# 06_LMS7002M_Power.net
KiCad netlist of a schematic drawn in Altium Designer
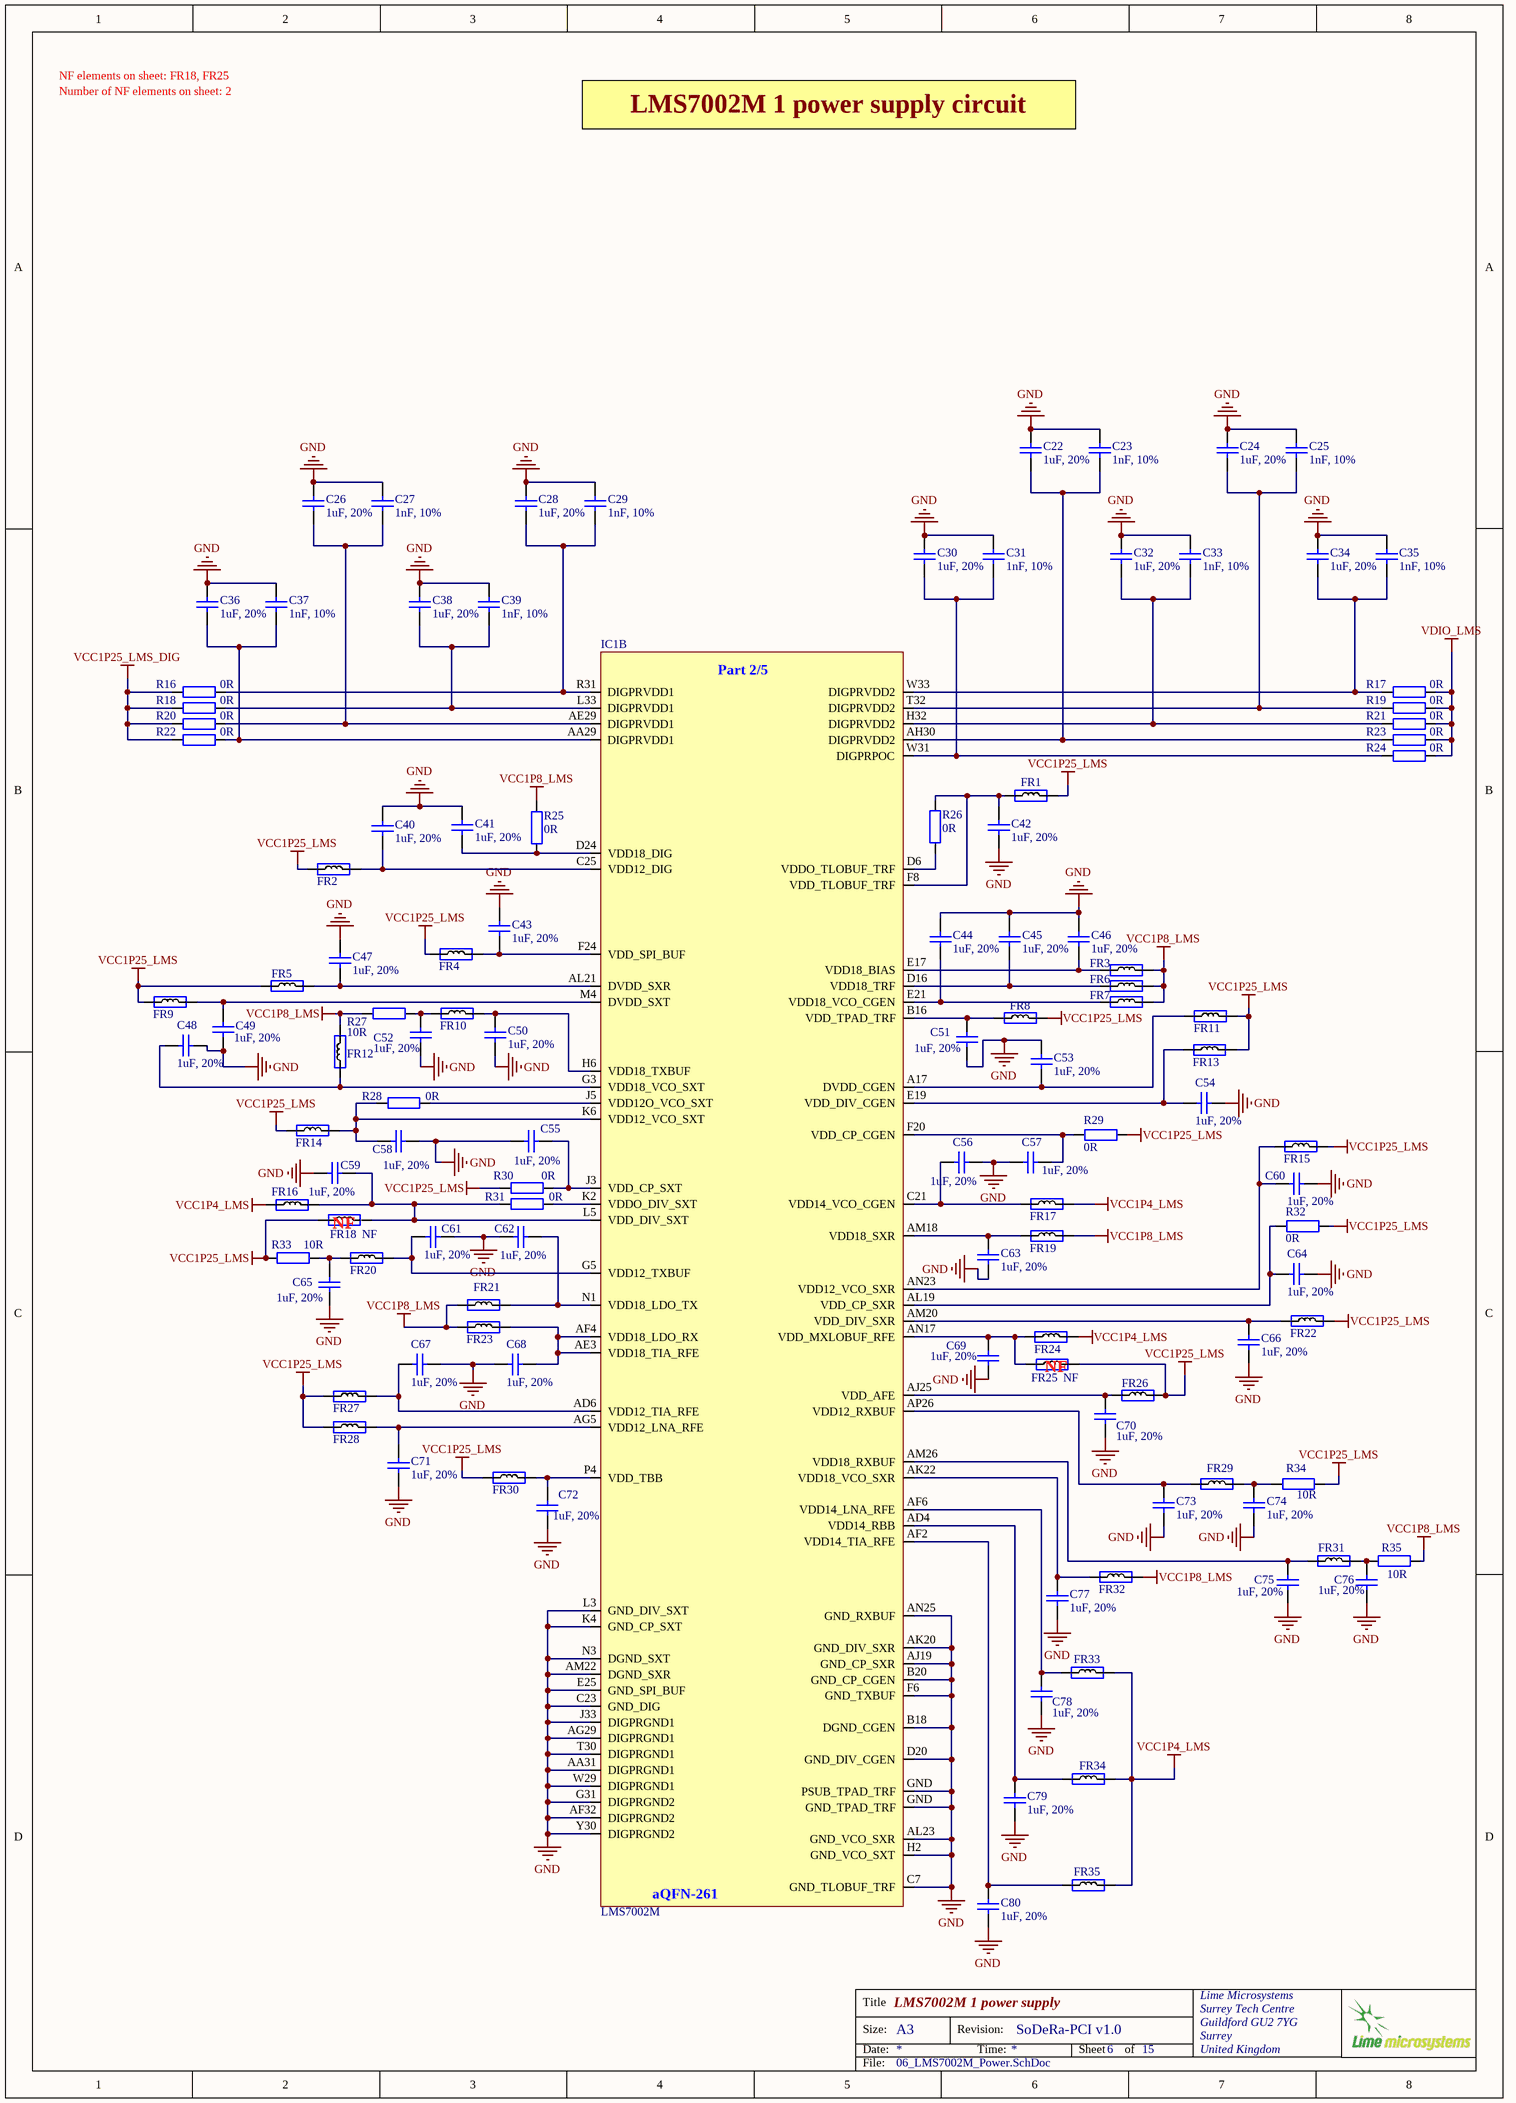
[diagram p0: 06_LMS7002M_Power.SchDoc]

(export (version "E")
  (design (tool "Eeschema 10.0.6"))
  (components
    (comp (ref "C22")
      (value "1uF, 20%")
      (footprint "LimeMicroAltiumLib_pcbLib:CAP0201")
      (fields (field (name "TOLERANCE") "±20%") (field (name "MANUFACTURER") "TDK Corporation"))
      (libsource (lib "LimeMicroAltiumLib_schLib") (part "Cap_0402"))
    )
    (comp (ref "C23")
      (value "1nF, 10%")
      (footprint "LimeMicroAltiumLib_pcbLib:CAP0201")
      (fields (field (name "TOLERANCE") "±10%") (field (name "MANUFACTURER") "TDK Corporation"))
      (libsource (lib "LimeMicroAltiumLib_schLib") (part "Cap_0402"))
    )
    (comp (ref "C24")
      (value "1uF, 20%")
      (footprint "LimeMicroAltiumLib_pcbLib:CAP0201")
      (fields (field (name "TOLERANCE") "±20%") (field (name "MANUFACTURER") "TDK Corporation"))
      (libsource (lib "LimeMicroAltiumLib_schLib") (part "Cap_0402"))
    )
    (comp (ref "C25")
      (value "1nF, 10%")
      (footprint "LimeMicroAltiumLib_pcbLib:CAP0201")
      (fields (field (name "TOLERANCE") "±10%") (field (name "MANUFACTURER") "TDK Corporation"))
      (libsource (lib "LimeMicroAltiumLib_schLib") (part "Cap_0402"))
    )
    (comp (ref "C26")
      (value "1uF, 20%")
      (footprint "LimeMicroAltiumLib_pcbLib:CAP0201")
      (fields (field (name "TOLERANCE") "±20%") (field (name "MANUFACTURER") "TDK Corporation"))
      (libsource (lib "LimeMicroAltiumLib_schLib") (part "Cap_0402"))
    )
    (comp (ref "C27")
      (value "1nF, 10%")
      (footprint "LimeMicroAltiumLib_pcbLib:CAP0201")
      (fields (field (name "TOLERANCE") "±10%") (field (name "MANUFACTURER") "TDK Corporation"))
      (libsource (lib "LimeMicroAltiumLib_schLib") (part "Cap_0402"))
    )
    (comp (ref "C28")
      (value "1uF, 20%")
      (footprint "LimeMicroAltiumLib_pcbLib:CAP0201")
      (fields (field (name "TOLERANCE") "±20%") (field (name "MANUFACTURER") "TDK Corporation"))
      (libsource (lib "LimeMicroAltiumLib_schLib") (part "Cap_0402"))
    )
    (comp (ref "C29")
      (value "1nF, 10%")
      (footprint "LimeMicroAltiumLib_pcbLib:CAP0201")
      (fields (field (name "TOLERANCE") "±10%") (field (name "MANUFACTURER") "TDK Corporation"))
      (libsource (lib "LimeMicroAltiumLib_schLib") (part "Cap_0402"))
    )
    (comp (ref "C30")
      (value "1uF, 20%")
      (footprint "LimeMicroAltiumLib_pcbLib:CAP0201")
      (fields (field (name "TOLERANCE") "±20%") (field (name "MANUFACTURER") "TDK Corporation"))
      (libsource (lib "LimeMicroAltiumLib_schLib") (part "Cap_0402"))
    )
    (comp (ref "C31")
      (value "1nF, 10%")
      (footprint "LimeMicroAltiumLib_pcbLib:CAP0201")
      (fields (field (name "TOLERANCE") "±10%") (field (name "MANUFACTURER") "TDK Corporation"))
      (libsource (lib "LimeMicroAltiumLib_schLib") (part "Cap_0402"))
    )
    (comp (ref "C32")
      (value "1uF, 20%")
      (footprint "LimeMicroAltiumLib_pcbLib:CAP0201")
      (fields (field (name "TOLERANCE") "±20%") (field (name "MANUFACTURER") "TDK Corporation"))
      (libsource (lib "LimeMicroAltiumLib_schLib") (part "Cap_0402"))
    )
    (comp (ref "C33")
      (value "1nF, 10%")
      (footprint "LimeMicroAltiumLib_pcbLib:CAP0201")
      (fields (field (name "TOLERANCE") "±10%") (field (name "MANUFACTURER") "TDK Corporation"))
      (libsource (lib "LimeMicroAltiumLib_schLib") (part "Cap_0402"))
    )
    (comp (ref "C34")
      (value "1uF, 20%")
      (footprint "LimeMicroAltiumLib_pcbLib:CAP0201")
      (fields (field (name "TOLERANCE") "±20%") (field (name "MANUFACTURER") "TDK Corporation"))
      (libsource (lib "LimeMicroAltiumLib_schLib") (part "Cap_0402"))
    )
    (comp (ref "C35")
      (value "1nF, 10%")
      (footprint "LimeMicroAltiumLib_pcbLib:CAP0201")
      (fields (field (name "TOLERANCE") "±10%") (field (name "MANUFACTURER") "TDK Corporation"))
      (libsource (lib "LimeMicroAltiumLib_schLib") (part "Cap_0402"))
    )
    (comp (ref "C36")
      (value "1uF, 20%")
      (footprint "LimeMicroAltiumLib_pcbLib:CAP0201")
      (fields (field (name "TOLERANCE") "±20%") (field (name "MANUFACTURER") "TDK Corporation"))
      (libsource (lib "LimeMicroAltiumLib_schLib") (part "Cap_0402"))
    )
    (comp (ref "C37")
      (value "1nF, 10%")
      (footprint "LimeMicroAltiumLib_pcbLib:CAP0201")
      (fields (field (name "TOLERANCE") "±10%") (field (name "MANUFACTURER") "TDK Corporation"))
      (libsource (lib "LimeMicroAltiumLib_schLib") (part "Cap_0402"))
    )
    (comp (ref "C38")
      (value "1uF, 20%")
      (footprint "LimeMicroAltiumLib_pcbLib:CAP0201")
      (fields (field (name "TOLERANCE") "±20%") (field (name "MANUFACTURER") "TDK Corporation"))
      (libsource (lib "LimeMicroAltiumLib_schLib") (part "Cap_0402"))
    )
    (comp (ref "C39")
      (value "1nF, 10%")
      (footprint "LimeMicroAltiumLib_pcbLib:CAP0201")
      (fields (field (name "TOLERANCE") "±10%") (field (name "MANUFACTURER") "TDK Corporation"))
      (libsource (lib "LimeMicroAltiumLib_schLib") (part "Cap_0402"))
    )
    (comp (ref "C40")
      (value "1uF, 20%")
      (footprint "LimeMicroAltiumLib_pcbLib:CAP0201")
      (fields (field (name "TOLERANCE") "±20%") (field (name "MANUFACTURER") "TDK Corporation"))
      (libsource (lib "LimeMicroAltiumLib_schLib") (part "Cap_0402"))
    )
    (comp (ref "C41")
      (value "1uF, 20%")
      (footprint "LimeMicroAltiumLib_pcbLib:CAP0201")
      (fields (field (name "TOLERANCE") "±20%") (field (name "MANUFACTURER") "TDK Corporation"))
      (libsource (lib "LimeMicroAltiumLib_schLib") (part "Cap_0402"))
    )
    (comp (ref "C42")
      (value "1uF, 20%")
      (footprint "LimeMicroAltiumLib_pcbLib:CAP0201")
      (fields (field (name "TOLERANCE") "±20%") (field (name "MANUFACTURER") "TDK Corporation"))
      (libsource (lib "LimeMicroAltiumLib_schLib") (part "Cap_0402"))
    )
    (comp (ref "C43")
      (value "1uF, 20%")
      (footprint "LimeMicroAltiumLib_pcbLib:CAP0201")
      (fields (field (name "TOLERANCE") "±20%") (field (name "MANUFACTURER") "TDK Corporation"))
      (libsource (lib "LimeMicroAltiumLib_schLib") (part "Cap_0402"))
    )
    (comp (ref "C44")
      (value "1uF, 20%")
      (footprint "LimeMicroAltiumLib_pcbLib:CAP0201")
      (fields (field (name "TOLERANCE") "±20%") (field (name "MANUFACTURER") "TDK Corporation"))
      (libsource (lib "LimeMicroAltiumLib_schLib") (part "Cap_0402"))
    )
    (comp (ref "C45")
      (value "1uF, 20%")
      (footprint "LimeMicroAltiumLib_pcbLib:CAP0201")
      (fields (field (name "TOLERANCE") "±20%") (field (name "MANUFACTURER") "TDK Corporation"))
      (libsource (lib "LimeMicroAltiumLib_schLib") (part "Cap_0402"))
    )
    (comp (ref "C46")
      (value "1uF, 20%")
      (footprint "LimeMicroAltiumLib_pcbLib:CAP0201")
      (fields (field (name "TOLERANCE") "±20%") (field (name "MANUFACTURER") "TDK Corporation"))
      (libsource (lib "LimeMicroAltiumLib_schLib") (part "Cap_0402"))
    )
    (comp (ref "C47")
      (value "1uF, 20%")
      (footprint "LimeMicroAltiumLib_pcbLib:CAP0201")
      (fields (field (name "TOLERANCE") "±20%") (field (name "MANUFACTURER") "TDK Corporation"))
      (libsource (lib "LimeMicroAltiumLib_schLib") (part "Cap_0402"))
    )
    (comp (ref "C48")
      (value "1uF, 20%")
      (footprint "LimeMicroAltiumLib_pcbLib:CAP0201")
      (fields (field (name "TOLERANCE") "±20%") (field (name "MANUFACTURER") "TDK Corporation"))
      (libsource (lib "LimeMicroAltiumLib_schLib") (part "Cap_0402"))
    )
    (comp (ref "C49")
      (value "1uF, 20%")
      (footprint "LimeMicroAltiumLib_pcbLib:CAP0201")
      (fields (field (name "TOLERANCE") "±20%") (field (name "MANUFACTURER") "TDK Corporation"))
      (libsource (lib "LimeMicroAltiumLib_schLib") (part "Cap_0402"))
    )
    (comp (ref "C50")
      (value "1uF, 20%")
      (footprint "LimeMicroAltiumLib_pcbLib:CAP0201")
      (fields (field (name "TOLERANCE") "±20%") (field (name "MANUFACTURER") "TDK Corporation"))
      (libsource (lib "LimeMicroAltiumLib_schLib") (part "Cap_0402"))
    )
    (comp (ref "C51")
      (value "1uF, 20%")
      (footprint "LimeMicroAltiumLib_pcbLib:CAP0201")
      (fields (field (name "TOLERANCE") "±20%") (field (name "MANUFACTURER") "TDK Corporation"))
      (libsource (lib "LimeMicroAltiumLib_schLib") (part "Cap_0402"))
    )
    (comp (ref "C52")
      (value "1uF, 20%")
      (footprint "LimeMicroAltiumLib_pcbLib:CAP0201")
      (fields (field (name "TOLERANCE") "±20%") (field (name "MANUFACTURER") "TDK Corporation"))
      (libsource (lib "LimeMicroAltiumLib_schLib") (part "Cap_0402"))
    )
    (comp (ref "C53")
      (value "1uF, 20%")
      (footprint "LimeMicroAltiumLib_pcbLib:CAP0201")
      (fields (field (name "TOLERANCE") "±20%") (field (name "MANUFACTURER") "TDK Corporation"))
      (libsource (lib "LimeMicroAltiumLib_schLib") (part "Cap_0402"))
    )
    (comp (ref "C54")
      (value "1uF, 20%")
      (footprint "LimeMicroAltiumLib_pcbLib:CAP0201")
      (fields (field (name "TOLERANCE") "±20%") (field (name "MANUFACTURER") "TDK Corporation"))
      (libsource (lib "LimeMicroAltiumLib_schLib") (part "Cap_0402"))
    )
    (comp (ref "C55")
      (value "1uF, 20%")
      (footprint "LimeMicroAltiumLib_pcbLib:CAP0201")
      (fields (field (name "TOLERANCE") "±20%") (field (name "MANUFACTURER") "TDK Corporation"))
      (libsource (lib "LimeMicroAltiumLib_schLib") (part "Cap_0402"))
    )
    (comp (ref "C56")
      (value "1uF, 20%")
      (footprint "LimeMicroAltiumLib_pcbLib:CAP0201")
      (fields (field (name "TOLERANCE") "±20%") (field (name "MANUFACTURER") "TDK Corporation"))
      (libsource (lib "LimeMicroAltiumLib_schLib") (part "Cap_0402"))
    )
    (comp (ref "C57")
      (value "1uF, 20%")
      (footprint "LimeMicroAltiumLib_pcbLib:CAP0201")
      (fields (field (name "TOLERANCE") "±20%") (field (name "MANUFACTURER") "TDK Corporation"))
      (libsource (lib "LimeMicroAltiumLib_schLib") (part "Cap_0402"))
    )
    (comp (ref "C58")
      (value "1uF, 20%")
      (footprint "LimeMicroAltiumLib_pcbLib:CAP0201")
      (fields (field (name "TOLERANCE") "±20%") (field (name "MANUFACTURER") "TDK Corporation"))
      (libsource (lib "LimeMicroAltiumLib_schLib") (part "Cap_0402"))
    )
    (comp (ref "C59")
      (value "1uF, 20%")
      (footprint "LimeMicroAltiumLib_pcbLib:CAP0201")
      (fields (field (name "TOLERANCE") "±20%") (field (name "MANUFACTURER") "TDK Corporation"))
      (libsource (lib "LimeMicroAltiumLib_schLib") (part "Cap_0402"))
    )
    (comp (ref "C60")
      (value "1uF, 20%")
      (footprint "LimeMicroAltiumLib_pcbLib:CAP0201")
      (fields (field (name "TOLERANCE") "±20%") (field (name "MANUFACTURER") "TDK Corporation"))
      (libsource (lib "LimeMicroAltiumLib_schLib") (part "Cap_0402"))
    )
    (comp (ref "C61")
      (value "1uF, 20%")
      (footprint "LimeMicroAltiumLib_pcbLib:CAP0201")
      (fields (field (name "TOLERANCE") "±20%") (field (name "MANUFACTURER") "TDK Corporation"))
      (libsource (lib "LimeMicroAltiumLib_schLib") (part "Cap_0402"))
    )
    (comp (ref "C62")
      (value "1uF, 20%")
      (footprint "LimeMicroAltiumLib_pcbLib:CAP0201")
      (fields (field (name "TOLERANCE") "±20%") (field (name "MANUFACTURER") "TDK Corporation"))
      (libsource (lib "LimeMicroAltiumLib_schLib") (part "Cap_0402"))
    )
    (comp (ref "C63")
      (value "1uF, 20%")
      (footprint "LimeMicroAltiumLib_pcbLib:CAP0201")
      (fields (field (name "TOLERANCE") "±20%") (field (name "MANUFACTURER") "TDK Corporation"))
      (libsource (lib "LimeMicroAltiumLib_schLib") (part "Cap_0402"))
    )
    (comp (ref "C64")
      (value "1uF, 20%")
      (footprint "LimeMicroAltiumLib_pcbLib:CAP0201")
      (fields (field (name "TOLERANCE") "±20%") (field (name "MANUFACTURER") "TDK Corporation"))
      (libsource (lib "LimeMicroAltiumLib_schLib") (part "Cap_0402"))
    )
    (comp (ref "C65")
      (value "1uF, 20%")
      (footprint "LimeMicroAltiumLib_pcbLib:CAP0201")
      (fields (field (name "TOLERANCE") "±20%") (field (name "MANUFACTURER") "TDK Corporation"))
      (libsource (lib "LimeMicroAltiumLib_schLib") (part "Cap_0402"))
    )
    (comp (ref "C66")
      (value "1uF, 20%")
      (footprint "LimeMicroAltiumLib_pcbLib:CAP0201")
      (fields (field (name "TOLERANCE") "±20%") (field (name "MANUFACTURER") "TDK Corporation"))
      (libsource (lib "LimeMicroAltiumLib_schLib") (part "Cap_0402"))
    )
    (comp (ref "C67")
      (value "1uF, 20%")
      (footprint "LimeMicroAltiumLib_pcbLib:CAP0201")
      (fields (field (name "TOLERANCE") "±20%") (field (name "MANUFACTURER") "TDK Corporation"))
      (libsource (lib "LimeMicroAltiumLib_schLib") (part "Cap_0402"))
    )
    (comp (ref "C68")
      (value "1uF, 20%")
      (footprint "LimeMicroAltiumLib_pcbLib:CAP0201")
      (fields (field (name "TOLERANCE") "±20%") (field (name "MANUFACTURER") "TDK Corporation"))
      (libsource (lib "LimeMicroAltiumLib_schLib") (part "Cap_0402"))
    )
    (comp (ref "C69")
      (value "1uF, 20%")
      (footprint "LimeMicroAltiumLib_pcbLib:CAP0201")
      (fields (field (name "TOLERANCE") "±20%") (field (name "MANUFACTURER") "TDK Corporation"))
      (libsource (lib "LimeMicroAltiumLib_schLib") (part "Cap_0402"))
    )
    (comp (ref "C70")
      (value "1uF, 20%")
      (footprint "LimeMicroAltiumLib_pcbLib:CAP0201")
      (fields (field (name "TOLERANCE") "±20%") (field (name "MANUFACTURER") "TDK Corporation"))
      (libsource (lib "LimeMicroAltiumLib_schLib") (part "Cap_0402"))
    )
    (comp (ref "C71")
      (value "1uF, 20%")
      (footprint "LimeMicroAltiumLib_pcbLib:CAP0201")
      (fields (field (name "TOLERANCE") "±20%") (field (name "MANUFACTURER") "TDK Corporation"))
      (libsource (lib "LimeMicroAltiumLib_schLib") (part "Cap_0402"))
    )
    (comp (ref "C72")
      (value "1uF, 20%")
      (footprint "LimeMicroAltiumLib_pcbLib:CAP0201")
      (fields (field (name "TOLERANCE") "±20%") (field (name "MANUFACTURER") "TDK Corporation"))
      (libsource (lib "LimeMicroAltiumLib_schLib") (part "Cap_0402"))
    )
    (comp (ref "C73")
      (value "1uF, 20%")
      (footprint "LimeMicroAltiumLib_pcbLib:CAP0201")
      (fields (field (name "TOLERANCE") "±20%") (field (name "MANUFACTURER") "TDK Corporation"))
      (libsource (lib "LimeMicroAltiumLib_schLib") (part "Cap_0402"))
    )
    (comp (ref "C74")
      (value "1uF, 20%")
      (footprint "LimeMicroAltiumLib_pcbLib:CAP0201")
      (fields (field (name "TOLERANCE") "±20%") (field (name "MANUFACTURER") "TDK Corporation"))
      (libsource (lib "LimeMicroAltiumLib_schLib") (part "Cap_0402"))
    )
    (comp (ref "C75")
      (value "1uF, 20%")
      (footprint "LimeMicroAltiumLib_pcbLib:CAP0201")
      (fields (field (name "TOLERANCE") "±20%") (field (name "MANUFACTURER") "TDK Corporation"))
      (libsource (lib "LimeMicroAltiumLib_schLib") (part "Cap_0402"))
    )
    (comp (ref "C76")
      (value "1uF, 20%")
      (footprint "LimeMicroAltiumLib_pcbLib:CAP0201")
      (fields (field (name "TOLERANCE") "±20%") (field (name "MANUFACTURER") "TDK Corporation"))
      (libsource (lib "LimeMicroAltiumLib_schLib") (part "Cap_0402"))
    )
    (comp (ref "C77")
      (value "1uF, 20%")
      (footprint "LimeMicroAltiumLib_pcbLib:CAP0201")
      (fields (field (name "TOLERANCE") "±20%") (field (name "MANUFACTURER") "TDK Corporation"))
      (libsource (lib "LimeMicroAltiumLib_schLib") (part "Cap_0402"))
    )
    (comp (ref "C78")
      (value "1uF, 20%")
      (footprint "LimeMicroAltiumLib_pcbLib:CAP0201")
      (fields (field (name "TOLERANCE") "±20%") (field (name "MANUFACTURER") "TDK Corporation"))
      (libsource (lib "LimeMicroAltiumLib_schLib") (part "Cap_0402"))
    )
    (comp (ref "C79")
      (value "1uF, 20%")
      (footprint "LimeMicroAltiumLib_pcbLib:CAP0201")
      (fields (field (name "TOLERANCE") "±20%") (field (name "MANUFACTURER") "TDK Corporation"))
      (libsource (lib "LimeMicroAltiumLib_schLib") (part "Cap_0402"))
    )
    (comp (ref "C80")
      (value "1uF, 20%")
      (footprint "LimeMicroAltiumLib_pcbLib:CAP0201")
      (fields (field (name "TOLERANCE") "±20%") (field (name "MANUFACTURER") "TDK Corporation"))
      (libsource (lib "LimeMicroAltiumLib_schLib") (part "Cap_0402"))
    )
    (comp (ref "FR1")
      (value "Ferrite")
      (footprint "LimeMicroAltiumLib_pcbLib:RES0201")
      (fields (field (name "MANUFACTURER") "Taiyo Yuden"))
      (libsource (lib "LimeMicroAltiumLib_schLib") (part "Ferrite"))
    )
    (comp (ref "FR2")
      (value "Ferrite")
      (footprint "LimeMicroAltiumLib_pcbLib:RES0201")
      (fields (field (name "MANUFACTURER") "Taiyo Yuden"))
      (libsource (lib "LimeMicroAltiumLib_schLib") (part "Ferrite"))
    )
    (comp (ref "FR3")
      (value "Ferrite")
      (footprint "LimeMicroAltiumLib_pcbLib:RES0201")
      (fields (field (name "MANUFACTURER") "Taiyo Yuden"))
      (libsource (lib "LimeMicroAltiumLib_schLib") (part "Ferrite"))
    )
    (comp (ref "FR4")
      (value "Ferrite")
      (footprint "LimeMicroAltiumLib_pcbLib:RES0201")
      (fields (field (name "MANUFACTURER") "Taiyo Yuden"))
      (libsource (lib "LimeMicroAltiumLib_schLib") (part "Ferrite"))
    )
    (comp (ref "FR5")
      (value "Ferrite")
      (footprint "LimeMicroAltiumLib_pcbLib:RES0201")
      (fields (field (name "MANUFACTURER") "Taiyo Yuden"))
      (libsource (lib "LimeMicroAltiumLib_schLib") (part "Ferrite"))
    )
    (comp (ref "FR6")
      (value "Ferrite")
      (footprint "LimeMicroAltiumLib_pcbLib:RES0201")
      (fields (field (name "MANUFACTURER") "Taiyo Yuden"))
      (libsource (lib "LimeMicroAltiumLib_schLib") (part "Ferrite"))
    )
    (comp (ref "FR7")
      (value "Ferrite")
      (footprint "LimeMicroAltiumLib_pcbLib:RES0201")
      (fields (field (name "MANUFACTURER") "Taiyo Yuden"))
      (libsource (lib "LimeMicroAltiumLib_schLib") (part "Ferrite"))
    )
    (comp (ref "FR8")
      (value "Ferrite")
      (footprint "LimeMicroAltiumLib_pcbLib:RES0201")
      (fields (field (name "MANUFACTURER") "Taiyo Yuden"))
      (libsource (lib "LimeMicroAltiumLib_schLib") (part "Ferrite"))
    )
    (comp (ref "FR9")
      (value "Ferrite")
      (footprint "LimeMicroAltiumLib_pcbLib:RES0201")
      (fields (field (name "MANUFACTURER") "Taiyo Yuden"))
      (libsource (lib "LimeMicroAltiumLib_schLib") (part "Ferrite"))
    )
    (comp (ref "FR10")
      (value "Ferrite")
      (footprint "LimeMicroAltiumLib_pcbLib:RES0201")
      (fields (field (name "MANUFACTURER") "Taiyo Yuden"))
      (libsource (lib "LimeMicroAltiumLib_schLib") (part "Ferrite"))
    )
    (comp (ref "FR11")
      (value "Ferrite")
      (footprint "LimeMicroAltiumLib_pcbLib:RES0201")
      (fields (field (name "MANUFACTURER") "Taiyo Yuden"))
      (libsource (lib "LimeMicroAltiumLib_schLib") (part "Ferrite"))
    )
    (comp (ref "FR12")
      (value "Ferrite")
      (footprint "LimeMicroAltiumLib_pcbLib:RES0201")
      (fields (field (name "MANUFACTURER") "Taiyo Yuden"))
      (libsource (lib "LimeMicroAltiumLib_schLib") (part "Ferrite"))
    )
    (comp (ref "FR13")
      (value "Ferrite")
      (footprint "LimeMicroAltiumLib_pcbLib:RES0201")
      (fields (field (name "MANUFACTURER") "Taiyo Yuden"))
      (libsource (lib "LimeMicroAltiumLib_schLib") (part "Ferrite"))
    )
    (comp (ref "FR14")
      (value "Ferrite")
      (footprint "LimeMicroAltiumLib_pcbLib:RES0201")
      (fields (field (name "MANUFACTURER") "Taiyo Yuden"))
      (libsource (lib "LimeMicroAltiumLib_schLib") (part "Ferrite"))
    )
    (comp (ref "FR15")
      (value "Ferrite")
      (footprint "LimeMicroAltiumLib_pcbLib:RES0201")
      (fields (field (name "MANUFACTURER") "Taiyo Yuden"))
      (libsource (lib "LimeMicroAltiumLib_schLib") (part "Ferrite"))
    )
    (comp (ref "FR16")
      (value "Ferrite")
      (footprint "LimeMicroAltiumLib_pcbLib:RES0201")
      (fields (field (name "MANUFACTURER") "Taiyo Yuden"))
      (libsource (lib "LimeMicroAltiumLib_schLib") (part "Ferrite"))
    )
    (comp (ref "FR17")
      (value "Ferrite")
      (footprint "LimeMicroAltiumLib_pcbLib:RES0201")
      (fields (field (name "MANUFACTURER") "Taiyo Yuden"))
      (libsource (lib "LimeMicroAltiumLib_schLib") (part "Ferrite"))
    )
    (comp (ref "FR18")
      (value "Ferrite")
      (footprint "LimeMicroAltiumLib_pcbLib:RES0201")
      (fields (field (name "MANUFACTURER") "Taiyo Yuden") (field (name "ASSEMBLY INFO") "NF"))
      (libsource (lib "LimeMicroAltiumLib_schLib") (part "Ferrite"))
    )
    (comp (ref "FR19")
      (value "Ferrite")
      (footprint "LimeMicroAltiumLib_pcbLib:RES0201")
      (fields (field (name "MANUFACTURER") "Taiyo Yuden"))
      (libsource (lib "LimeMicroAltiumLib_schLib") (part "Ferrite"))
    )
    (comp (ref "FR20")
      (value "Ferrite")
      (footprint "LimeMicroAltiumLib_pcbLib:RES0201")
      (fields (field (name "MANUFACTURER") "Taiyo Yuden"))
      (libsource (lib "LimeMicroAltiumLib_schLib") (part "Ferrite"))
    )
    (comp (ref "FR21")
      (value "Ferrite")
      (footprint "LimeMicroAltiumLib_pcbLib:RES0201")
      (fields (field (name "MANUFACTURER") "Taiyo Yuden"))
      (libsource (lib "LimeMicroAltiumLib_schLib") (part "Ferrite"))
    )
    (comp (ref "FR22")
      (value "Ferrite")
      (footprint "LimeMicroAltiumLib_pcbLib:RES0201")
      (fields (field (name "MANUFACTURER") "Taiyo Yuden"))
      (libsource (lib "LimeMicroAltiumLib_schLib") (part "Ferrite"))
    )
    (comp (ref "FR23")
      (value "Ferrite")
      (footprint "LimeMicroAltiumLib_pcbLib:RES0201")
      (fields (field (name "MANUFACTURER") "Taiyo Yuden"))
      (libsource (lib "LimeMicroAltiumLib_schLib") (part "Ferrite"))
    )
    (comp (ref "FR24")
      (value "Ferrite")
      (footprint "LimeMicroAltiumLib_pcbLib:RES0201")
      (fields (field (name "MANUFACTURER") "Taiyo Yuden"))
      (libsource (lib "LimeMicroAltiumLib_schLib") (part "Ferrite"))
    )
    (comp (ref "FR25")
      (value "Ferrite")
      (footprint "LimeMicroAltiumLib_pcbLib:RES0201")
      (fields (field (name "MANUFACTURER") "Taiyo Yuden") (field (name "ASSEMBLY INFO") "NF"))
      (libsource (lib "LimeMicroAltiumLib_schLib") (part "Ferrite"))
    )
    (comp (ref "FR26")
      (value "Ferrite")
      (footprint "LimeMicroAltiumLib_pcbLib:RES0201")
      (fields (field (name "MANUFACTURER") "Taiyo Yuden"))
      (libsource (lib "LimeMicroAltiumLib_schLib") (part "Ferrite"))
    )
    (comp (ref "FR27")
      (value "Ferrite")
      (footprint "LimeMicroAltiumLib_pcbLib:RES0201")
      (fields (field (name "MANUFACTURER") "Taiyo Yuden"))
      (libsource (lib "LimeMicroAltiumLib_schLib") (part "Ferrite"))
    )
    (comp (ref "FR28")
      (value "Ferrite")
      (footprint "LimeMicroAltiumLib_pcbLib:RES0201")
      (fields (field (name "MANUFACTURER") "Taiyo Yuden"))
      (libsource (lib "LimeMicroAltiumLib_schLib") (part "Ferrite"))
    )
    (comp (ref "FR29")
      (value "Ferrite")
      (footprint "LimeMicroAltiumLib_pcbLib:RES0201")
      (fields (field (name "MANUFACTURER") "Taiyo Yuden"))
      (libsource (lib "LimeMicroAltiumLib_schLib") (part "Ferrite"))
    )
    (comp (ref "FR30")
      (value "Ferrite")
      (footprint "LimeMicroAltiumLib_pcbLib:RES0201")
      (fields (field (name "MANUFACTURER") "Taiyo Yuden"))
      (libsource (lib "LimeMicroAltiumLib_schLib") (part "Ferrite"))
    )
    (comp (ref "FR31")
      (value "Ferrite")
      (footprint "LimeMicroAltiumLib_pcbLib:RES0201")
      (fields (field (name "MANUFACTURER") "Taiyo Yuden"))
      (libsource (lib "LimeMicroAltiumLib_schLib") (part "Ferrite"))
    )
    (comp (ref "FR32")
      (value "Ferrite")
      (footprint "LimeMicroAltiumLib_pcbLib:RES0201")
      (fields (field (name "MANUFACTURER") "Taiyo Yuden"))
      (libsource (lib "LimeMicroAltiumLib_schLib") (part "Ferrite"))
    )
    (comp (ref "FR33")
      (value "Ferrite")
      (footprint "LimeMicroAltiumLib_pcbLib:RES0201")
      (fields (field (name "MANUFACTURER") "Taiyo Yuden"))
      (libsource (lib "LimeMicroAltiumLib_schLib") (part "Ferrite"))
    )
    (comp (ref "FR34")
      (value "Ferrite")
      (footprint "LimeMicroAltiumLib_pcbLib:RES0201")
      (fields (field (name "MANUFACTURER") "Taiyo Yuden"))
      (libsource (lib "LimeMicroAltiumLib_schLib") (part "Ferrite"))
    )
    (comp (ref "FR35")
      (value "Ferrite")
      (footprint "LimeMicroAltiumLib_pcbLib:RES0201")
      (fields (field (name "MANUFACTURER") "Taiyo Yuden"))
      (libsource (lib "LimeMicroAltiumLib_schLib") (part "Ferrite"))
    )
    (comp (ref "IC1")
      (value "LMS7002M")
      (footprint "LimeMicroAltiumLib_pcbLib:LMS7002M")
      (libsource (lib "LimeMicroAltiumLib_schLib") (part "LMS7002M"))
    )
    (comp (ref "R16")
      (value "0R")
      (footprint "LimeMicroAltiumLib_pcbLib:RES0402")
      (fields (field (name "MANUFACTURER") "Yageo") (field (name "TOLERANCE") "Jumper"))
      (libsource (lib "LimeMicroAltiumLib_schLib") (part "Res_0402"))
    )
    (comp (ref "R17")
      (value "0R")
      (footprint "LimeMicroAltiumLib_pcbLib:RES0402")
      (fields (field (name "MANUFACTURER") "Yageo") (field (name "TOLERANCE") "Jumper"))
      (libsource (lib "LimeMicroAltiumLib_schLib") (part "Res_0402"))
    )
    (comp (ref "R18")
      (value "0R")
      (footprint "LimeMicroAltiumLib_pcbLib:RES0402")
      (fields (field (name "MANUFACTURER") "Yageo") (field (name "TOLERANCE") "Jumper"))
      (libsource (lib "LimeMicroAltiumLib_schLib") (part "Res_0402"))
    )
    (comp (ref "R19")
      (value "0R")
      (footprint "LimeMicroAltiumLib_pcbLib:RES0402")
      (fields (field (name "MANUFACTURER") "Yageo") (field (name "TOLERANCE") "Jumper"))
      (libsource (lib "LimeMicroAltiumLib_schLib") (part "Res_0402"))
    )
    (comp (ref "R20")
      (value "0R")
      (footprint "LimeMicroAltiumLib_pcbLib:RES0402")
      (fields (field (name "MANUFACTURER") "Yageo") (field (name "TOLERANCE") "Jumper"))
      (libsource (lib "LimeMicroAltiumLib_schLib") (part "Res_0402"))
    )
    (comp (ref "R21")
      (value "0R")
      (footprint "LimeMicroAltiumLib_pcbLib:RES0402")
      (fields (field (name "MANUFACTURER") "Yageo") (field (name "TOLERANCE") "Jumper"))
      (libsource (lib "LimeMicroAltiumLib_schLib") (part "Res_0402"))
    )
    (comp (ref "R22")
      (value "0R")
      (footprint "LimeMicroAltiumLib_pcbLib:RES0402")
      (fields (field (name "MANUFACTURER") "Yageo") (field (name "TOLERANCE") "Jumper"))
      (libsource (lib "LimeMicroAltiumLib_schLib") (part "Res_0402"))
    )
    (comp (ref "R23")
      (value "0R")
      (footprint "LimeMicroAltiumLib_pcbLib:RES0402")
      (fields (field (name "MANUFACTURER") "Yageo") (field (name "TOLERANCE") "Jumper"))
      (libsource (lib "LimeMicroAltiumLib_schLib") (part "Res_0402"))
    )
    (comp (ref "R24")
      (value "0R")
      (footprint "LimeMicroAltiumLib_pcbLib:RES0402")
      (fields (field (name "MANUFACTURER") "Yageo") (field (name "TOLERANCE") "Jumper"))
      (libsource (lib "LimeMicroAltiumLib_schLib") (part "Res_0402"))
    )
    (comp (ref "R25")
      (value "0R")
      (footprint "LimeMicroAltiumLib_pcbLib:RES0201")
      (fields (field (name "MANUFACTURER") "Rohm Semiconductor") (field (name "TOLERANCE") "Jumper"))
      (libsource (lib "LimeMicroAltiumLib_schLib") (part "Res_0402"))
    )
    (comp (ref "R26")
      (value "0R")
      (footprint "LimeMicroAltiumLib_pcbLib:RES0201")
      (fields (field (name "MANUFACTURER") "Rohm Semiconductor") (field (name "TOLERANCE") "Jumper"))
      (libsource (lib "LimeMicroAltiumLib_schLib") (part "Res_0402"))
    )
    (comp (ref "R27")
      (value "10R")
      (footprint "LimeMicroAltiumLib_pcbLib:RES0201")
      (fields
        (field (name "MANUFACTURER") "Panasonic Electronic Components")
        (field (name "TOLERANCE") "±1%")
        (field (name "MANUFACTURER PART NUMBER") "ERJ-1GEF10R0C")
      )
      (libsource (lib "LimeMicroAltiumLib_schLib") (part "Res_0402"))
    )
    (comp (ref "R28")
      (value "0R")
      (footprint "LimeMicroAltiumLib_pcbLib:RES0201")
      (fields (field (name "MANUFACTURER") "Rohm Semiconductor") (field (name "TOLERANCE") "Jumper"))
      (libsource (lib "LimeMicroAltiumLib_schLib") (part "Res_0402"))
    )
    (comp (ref "R29")
      (value "0R")
      (footprint "LimeMicroAltiumLib_pcbLib:RES0201")
      (fields (field (name "MANUFACTURER") "Rohm Semiconductor") (field (name "TOLERANCE") "Jumper"))
      (libsource (lib "LimeMicroAltiumLib_schLib") (part "Res_0402"))
    )
    (comp (ref "R30")
      (value "0R")
      (footprint "LimeMicroAltiumLib_pcbLib:RES0201")
      (fields (field (name "MANUFACTURER") "Rohm Semiconductor") (field (name "TOLERANCE") "Jumper"))
      (libsource (lib "LimeMicroAltiumLib_schLib") (part "Res_0402"))
    )
    (comp (ref "R31")
      (value "0R")
      (footprint "LimeMicroAltiumLib_pcbLib:RES0201")
      (fields (field (name "MANUFACTURER") "Rohm Semiconductor") (field (name "TOLERANCE") "Jumper"))
      (libsource (lib "LimeMicroAltiumLib_schLib") (part "Res_0402"))
    )
    (comp (ref "R32")
      (value "0R")
      (footprint "LimeMicroAltiumLib_pcbLib:RES0201")
      (fields (field (name "MANUFACTURER") "Rohm Semiconductor") (field (name "TOLERANCE") "Jumper"))
      (libsource (lib "LimeMicroAltiumLib_schLib") (part "Res_0402"))
    )
    (comp (ref "R33")
      (value "10R")
      (footprint "LimeMicroAltiumLib_pcbLib:RES0201")
      (fields
        (field (name "MANUFACTURER") "Panasonic Electronic Components")
        (field (name "TOLERANCE") "±1%")
        (field (name "MANUFACTURER PART NUMBER") "ERJ-1GEF10R0C")
      )
      (libsource (lib "LimeMicroAltiumLib_schLib") (part "Res_0402"))
    )
    (comp (ref "R34")
      (value "10R")
      (footprint "LimeMicroAltiumLib_pcbLib:RES0201")
      (fields
        (field (name "MANUFACTURER") "Panasonic Electronic Components")
        (field (name "TOLERANCE") "±1%")
        (field (name "MANUFACTURER PART NUMBER") "ERJ-1GEF10R0C")
      )
      (libsource (lib "LimeMicroAltiumLib_schLib") (part "Res_0402"))
    )
    (comp (ref "R35")
      (value "10R")
      (footprint "LimeMicroAltiumLib_pcbLib:RES0201")
      (fields
        (field (name "MANUFACTURER") "Panasonic Electronic Components")
        (field (name "TOLERANCE") "±1%")
        (field (name "MANUFACTURER PART NUMBER") "ERJ-1GEF10R0C")
      )
      (libsource (lib "LimeMicroAltiumLib_schLib") (part "Res_0402"))
    )
  )
  (nets
    (net (code "1") (name "GND") (class "Default")
      (node (ref "C22") (pin "2") (pinfunction "2_2") (pintype "passive"))
      (node (ref "C23") (pin "2") (pinfunction "2_2") (pintype "passive"))
      (node (ref "C24") (pin "2") (pinfunction "2_2") (pintype "passive"))
      (node (ref "C25") (pin "2") (pinfunction "2_2") (pintype "passive"))
      (node (ref "C26") (pin "2") (pinfunction "2_2") (pintype "passive"))
      (node (ref "C27") (pin "2") (pinfunction "2_2") (pintype "passive"))
      (node (ref "C28") (pin "2") (pinfunction "2_2") (pintype "passive"))
      (node (ref "C29") (pin "2") (pinfunction "2_2") (pintype "passive"))
      (node (ref "C30") (pin "2") (pinfunction "2_2") (pintype "passive"))
      (node (ref "C31") (pin "2") (pinfunction "2_2") (pintype "passive"))
      (node (ref "C32") (pin "2") (pinfunction "2_2") (pintype "passive"))
      (node (ref "C33") (pin "2") (pinfunction "2_2") (pintype "passive"))
      (node (ref "C34") (pin "2") (pinfunction "2_2") (pintype "passive"))
      (node (ref "C35") (pin "2") (pinfunction "2_2") (pintype "passive"))
      (node (ref "C36") (pin "2") (pinfunction "2_2") (pintype "passive"))
      (node (ref "C37") (pin "2") (pinfunction "2_2") (pintype "passive"))
      (node (ref "C38") (pin "2") (pinfunction "2_2") (pintype "passive"))
      (node (ref "C39") (pin "2") (pinfunction "2_2") (pintype "passive"))
      (node (ref "C40") (pin "2") (pinfunction "2_2") (pintype "passive"))
      (node (ref "C41") (pin "2") (pinfunction "2_2") (pintype "passive"))
      (node (ref "C42") (pin "2") (pinfunction "2_2") (pintype "passive"))
      (node (ref "C43") (pin "2") (pinfunction "2_2") (pintype "passive"))
      (node (ref "C44") (pin "2") (pinfunction "2_2") (pintype "passive"))
      (node (ref "C45") (pin "2") (pinfunction "2_2") (pintype "passive"))
      (node (ref "C46") (pin "2") (pinfunction "2_2") (pintype "passive"))
      (node (ref "C47") (pin "2") (pinfunction "2_2") (pintype "passive"))
      (node (ref "C48") (pin "2") (pinfunction "2_2") (pintype "passive"))
      (node (ref "C49") (pin "2") (pinfunction "2_2") (pintype "passive"))
      (node (ref "C50") (pin "2") (pinfunction "2_2") (pintype "passive"))
      (node (ref "C51") (pin "2") (pinfunction "2_2") (pintype "passive"))
      (node (ref "C52") (pin "2") (pinfunction "2_2") (pintype "passive"))
      (node (ref "C53") (pin "2") (pinfunction "2_2") (pintype "passive"))
      (node (ref "C54") (pin "2") (pinfunction "2_2") (pintype "passive"))
      (node (ref "C55") (pin "2") (pinfunction "2_2") (pintype "passive"))
      (node (ref "C56") (pin "2") (pinfunction "2_2") (pintype "passive"))
      (node (ref "C57") (pin "2") (pinfunction "2_2") (pintype "passive"))
      (node (ref "C58") (pin "1") (pinfunction "1_1") (pintype "passive"))
      (node (ref "C59") (pin "2") (pinfunction "2_2") (pintype "passive"))
      (node (ref "C60") (pin "2") (pinfunction "2_2") (pintype "passive"))
      (node (ref "C61") (pin "2") (pinfunction "2_2") (pintype "passive"))
      (node (ref "C62") (pin "2") (pinfunction "2_2") (pintype "passive"))
      (node (ref "C63") (pin "2") (pinfunction "2_2") (pintype "passive"))
      (node (ref "C64") (pin "2") (pinfunction "2_2") (pintype "passive"))
      (node (ref "C65") (pin "2") (pinfunction "2_2") (pintype "passive"))
      (node (ref "C66") (pin "2") (pinfunction "2_2") (pintype "passive"))
      (node (ref "C67") (pin "2") (pinfunction "2_2") (pintype "passive"))
      (node (ref "C68") (pin "2") (pinfunction "2_2") (pintype "passive"))
      (node (ref "C69") (pin "2") (pinfunction "2_2") (pintype "passive"))
      (node (ref "C70") (pin "2") (pinfunction "2_2") (pintype "passive"))
      (node (ref "C71") (pin "2") (pinfunction "2_2") (pintype "passive"))
      (node (ref "C72") (pin "2") (pinfunction "2_2") (pintype "passive"))
      (node (ref "C73") (pin "2") (pinfunction "2_2") (pintype "passive"))
      (node (ref "C74") (pin "2") (pinfunction "2_2") (pintype "passive"))
      (node (ref "C75") (pin "2") (pinfunction "2_2") (pintype "passive"))
      (node (ref "C76") (pin "2") (pinfunction "2_2") (pintype "passive"))
      (node (ref "C77") (pin "2") (pinfunction "2_2") (pintype "passive"))
      (node (ref "C78") (pin "2") (pinfunction "2_2") (pintype "passive"))
      (node (ref "C79") (pin "2") (pinfunction "2_2") (pintype "passive"))
      (node (ref "C80") (pin "2") (pinfunction "2_2") (pintype "passive"))
      (node (ref "IC1") (pin "AA31") (pinfunction "DIGPRGND1_AA31") (pintype "passive"))
      (node (ref "IC1") (pin "AF32") (pinfunction "DIGPRGND2_AF32") (pintype "passive"))
      (node (ref "IC1") (pin "AG29") (pinfunction "DIGPRGND1_AG29") (pintype "passive"))
      (node (ref "IC1") (pin "AJ19") (pinfunction "GND_CP_SXR_AJ19") (pintype "passive"))
      (node (ref "IC1") (pin "AK20") (pinfunction "GND_DIV_SXR_AK20") (pintype "passive"))
      (node (ref "IC1") (pin "AL23") (pinfunction "GND_VCO_SXR_AL23") (pintype "passive"))
      (node (ref "IC1") (pin "AM22") (pinfunction "DGND_SXR_AM22") (pintype "passive"))
      (node (ref "IC1") (pin "AN25") (pinfunction "GND_RXBUF_AN25") (pintype "passive"))
      (node (ref "IC1") (pin "B18") (pinfunction "DGND_CGEN_B18") (pintype "passive"))
      (node (ref "IC1") (pin "B20") (pinfunction "GND_CP_CGEN_B20") (pintype "passive"))
      (node (ref "IC1") (pin "C23") (pinfunction "GND_DIG_C23") (pintype "passive"))
      (node (ref "IC1") (pin "C7") (pinfunction "GND_TLOBUF_TRF_C7") (pintype "passive"))
      (node (ref "IC1") (pin "D20") (pinfunction "GND_DIV_CGEN_D20") (pintype "passive"))
      (node (ref "IC1") (pin "E25") (pinfunction "GND_SPI_BUF_E25") (pintype "passive"))
      (node (ref "IC1") (pin "F6") (pinfunction "GND_TXBUF_F6") (pintype "passive"))
      (node (ref "IC1") (pin "G31") (pinfunction "DIGPRGND2_G31") (pintype "passive"))
      (node (ref "IC1") (pin "GND") (pinfunction "PSUB_TPAD_TRF_GND") (pintype "passive"))
      (node (ref "IC1") (pin "H2") (pinfunction "GND_VCO_SXT_H2") (pintype "passive"))
      (node (ref "IC1") (pin "J33") (pinfunction "DIGPRGND1_J33") (pintype "passive"))
      (node (ref "IC1") (pin "K4") (pinfunction "GND_CP_SXT_K4") (pintype "passive"))
      (node (ref "IC1") (pin "L3") (pinfunction "GND_DIV_SXT_L3") (pintype "passive"))
      (node (ref "IC1") (pin "N3") (pinfunction "DGND_SXT_N3") (pintype "passive"))
      (node (ref "IC1") (pin "T30") (pinfunction "DIGPRGND1_T30") (pintype "passive"))
      (node (ref "IC1") (pin "W29") (pinfunction "DIGPRGND1_W29") (pintype "passive"))
      (node (ref "IC1") (pin "Y30") (pinfunction "DIGPRGND2_Y30") (pintype "passive"))
    )
    (net (code "2") (name "Net-(C22-Pad1)") (class "Default")
      (node (ref "C22") (pin "1") (pinfunction "1_1") (pintype "passive"))
      (node (ref "C23") (pin "1") (pinfunction "1_1") (pintype "passive"))
      (node (ref "IC1") (pin "AH30") (pinfunction "DIGPRVDD2_AH30") (pintype "passive"))
      (node (ref "R23") (pin "2") (pinfunction "2_2") (pintype "passive"))
    )
    (net (code "3") (name "Net-(C24-Pad1)") (class "Default")
      (node (ref "C24") (pin "1") (pinfunction "1_1") (pintype "passive"))
      (node (ref "C25") (pin "1") (pinfunction "1_1") (pintype "passive"))
      (node (ref "IC1") (pin "T32") (pinfunction "DIGPRVDD2_T32") (pintype "passive"))
      (node (ref "R19") (pin "2") (pinfunction "2_2") (pintype "passive"))
    )
    (net (code "4") (name "Net-(C26-Pad1)") (class "Default")
      (node (ref "C26") (pin "1") (pinfunction "1_1") (pintype "passive"))
      (node (ref "C27") (pin "1") (pinfunction "1_1") (pintype "passive"))
      (node (ref "IC1") (pin "AE29") (pinfunction "DIGPRVDD1_AE29") (pintype "passive"))
      (node (ref "R20") (pin "1") (pinfunction "1_1") (pintype "passive"))
    )
    (net (code "5") (name "Net-(C28-Pad1)") (class "Default")
      (node (ref "C28") (pin "1") (pinfunction "1_1") (pintype "passive"))
      (node (ref "C29") (pin "1") (pinfunction "1_1") (pintype "passive"))
      (node (ref "IC1") (pin "R31") (pinfunction "DIGPRVDD1_R31") (pintype "passive"))
      (node (ref "R16") (pin "1") (pinfunction "1_1") (pintype "passive"))
    )
    (net (code "6") (name "Net-(C32-Pad1)") (class "Default")
      (node (ref "C32") (pin "1") (pinfunction "1_1") (pintype "passive"))
      (node (ref "C33") (pin "1") (pinfunction "1_1") (pintype "passive"))
      (node (ref "IC1") (pin "H32") (pinfunction "DIGPRVDD2_H32") (pintype "passive"))
      (node (ref "R21") (pin "2") (pinfunction "2_2") (pintype "passive"))
    )
    (net (code "7") (name "Net-(C34-Pad1)") (class "Default")
      (node (ref "C34") (pin "1") (pinfunction "1_1") (pintype "passive"))
      (node (ref "C35") (pin "1") (pinfunction "1_1") (pintype "passive"))
      (node (ref "IC1") (pin "W33") (pinfunction "DIGPRVDD2_W33") (pintype "passive"))
      (node (ref "R17") (pin "2") (pinfunction "2_2") (pintype "passive"))
    )
    (net (code "8") (name "Net-(C36-Pad1)") (class "Default")
      (node (ref "C36") (pin "1") (pinfunction "1_1") (pintype "passive"))
      (node (ref "C37") (pin "1") (pinfunction "1_1") (pintype "passive"))
      (node (ref "IC1") (pin "AA29") (pinfunction "DIGPRVDD1_AA29") (pintype "passive"))
      (node (ref "R22") (pin "1") (pinfunction "1_1") (pintype "passive"))
    )
    (net (code "9") (name "Net-(C38-Pad1)") (class "Default")
      (node (ref "C38") (pin "1") (pinfunction "1_1") (pintype "passive"))
      (node (ref "C39") (pin "1") (pinfunction "1_1") (pintype "passive"))
      (node (ref "IC1") (pin "L33") (pinfunction "DIGPRVDD1_L33") (pintype "passive"))
      (node (ref "R18") (pin "1") (pinfunction "1_1") (pintype "passive"))
    )
    (net (code "10") (name "Net-(C52-Pad1)") (class "Default")
      (node (ref "C52") (pin "1") (pinfunction "1_1") (pintype "passive"))
      (node (ref "FR10") (pin "1") (pinfunction "1_1") (pintype "passive"))
      (node (ref "R27") (pin "1") (pinfunction "1_1") (pintype "passive"))
    )
    (net (code "11") (name "Net-(C65-Pad1)") (class "Default")
      (node (ref "C65") (pin "1") (pinfunction "1_1") (pintype "passive"))
      (node (ref "FR20") (pin "1") (pinfunction "1_1") (pintype "passive"))
      (node (ref "R33") (pin "1") (pinfunction "1_1") (pintype "passive"))
    )
    (net (code "12") (name "Net-(C74-Pad1)") (class "Default")
      (node (ref "C74") (pin "1") (pinfunction "1_1") (pintype "passive"))
      (node (ref "FR29") (pin "2") (pinfunction "2_2") (pintype "passive"))
      (node (ref "R34") (pin "2") (pinfunction "2_2") (pintype "passive"))
    )
    (net (code "13") (name "Net-(C76-Pad1)") (class "Default")
      (node (ref "C76") (pin "1") (pinfunction "1_1") (pintype "passive"))
      (node (ref "FR31") (pin "2") (pinfunction "2_2") (pintype "passive"))
      (node (ref "R35") (pin "2") (pinfunction "2_2") (pintype "passive"))
    )
    (net (code "14") (name "Net-(IC1B-DIGPRPOC)") (class "Default")
      (node (ref "C30") (pin "1") (pinfunction "1_1") (pintype "passive"))
      (node (ref "C31") (pin "1") (pinfunction "1_1") (pintype "passive"))
      (node (ref "IC1") (pin "W31") (pinfunction "DIGPRPOC_W31") (pintype "passive"))
      (node (ref "R24") (pin "2") (pinfunction "2_2") (pintype "passive"))
    )
    (net (code "15") (name "Net-(IC1B-DVDD_CGEN)") (class "Default")
      (node (ref "C53") (pin "1") (pinfunction "1_1") (pintype "passive"))
      (node (ref "FR11") (pin "1") (pinfunction "1_1") (pintype "passive"))
      (node (ref "IC1") (pin "A17") (pinfunction "DVDD_CGEN_A17") (pintype "passive"))
    )
    (net (code "16") (name "Net-(IC1B-DVDD_SXR)") (class "Default")
      (node (ref "C47") (pin "1") (pinfunction "1_1") (pintype "passive"))
      (node (ref "FR5") (pin "2") (pinfunction "2_2") (pintype "passive"))
      (node (ref "IC1") (pin "AL21") (pinfunction "DVDD_SXR_AL21") (pintype "passive"))
    )
    (net (code "17") (name "Net-(IC1B-DVDD_SXT)") (class "Default")
      (node (ref "C49") (pin "1") (pinfunction "1_1") (pintype "passive"))
      (node (ref "FR9") (pin "2") (pinfunction "2_2") (pintype "passive"))
      (node (ref "IC1") (pin "M4") (pinfunction "DVDD_SXT_M4") (pintype "passive"))
    )
    (net (code "18") (name "Net-(IC1B-VDD12O_VCO_SXT)") (class "Default")
      (node (ref "IC1") (pin "J5") (pinfunction "VDD12O_VCO_SXT_J5") (pintype "passive"))
      (node (ref "R28") (pin "1") (pinfunction "1_1") (pintype "passive"))
    )
    (net (code "19") (name "Net-(IC1B-VDD12_DIG)") (class "Default")
      (node (ref "C40") (pin "1") (pinfunction "1_1") (pintype "passive"))
      (node (ref "FR2") (pin "2") (pinfunction "2_2") (pintype "passive"))
      (node (ref "IC1") (pin "C25") (pinfunction "VDD12_DIG_C25") (pintype "passive"))
    )
    (net (code "20") (name "Net-(IC1B-VDD12_LNA_RFE)") (class "Default")
      (node (ref "C71") (pin "1") (pinfunction "1_1") (pintype "passive"))
      (node (ref "FR28") (pin "2") (pinfunction "2_2") (pintype "passive"))
      (node (ref "IC1") (pin "AG5") (pinfunction "VDD12_LNA_RFE_AG5") (pintype "passive"))
    )
    (net (code "21") (name "Net-(IC1B-VDD12_RXBUF)") (class "Default")
      (node (ref "C73") (pin "1") (pinfunction "1_1") (pintype "passive"))
      (node (ref "FR29") (pin "1") (pinfunction "1_1") (pintype "passive"))
      (node (ref "IC1") (pin "AP26") (pinfunction "VDD12_RXBUF_AP26") (pintype "passive"))
    )
    (net (code "22") (name "Net-(IC1B-VDD12_TIA_RFE)") (class "Default")
      (node (ref "C67") (pin "1") (pinfunction "1_1") (pintype "passive"))
      (node (ref "FR27") (pin "2") (pinfunction "2_2") (pintype "passive"))
      (node (ref "IC1") (pin "AD6") (pinfunction "VDD12_TIA_RFE_AD6") (pintype "passive"))
    )
    (net (code "23") (name "Net-(IC1B-VDD12_TXBUF)") (class "Default")
      (node (ref "C61") (pin "1") (pinfunction "1_1") (pintype "passive"))
      (node (ref "FR20") (pin "2") (pinfunction "2_2") (pintype "passive"))
      (node (ref "IC1") (pin "G5") (pinfunction "VDD12_TXBUF_G5") (pintype "passive"))
    )
    (net (code "24") (name "Net-(IC1B-VDD12_VCO_SXR)") (class "Default")
      (node (ref "C60") (pin "1") (pinfunction "1_1") (pintype "passive"))
      (node (ref "FR15") (pin "1") (pinfunction "1_1") (pintype "passive"))
      (node (ref "IC1") (pin "AN23") (pinfunction "VDD12_VCO_SXR_AN23") (pintype "passive"))
    )
    (net (code "25") (name "Net-(IC1B-VDD12_VCO_SXT)") (class "Default")
      (node (ref "C58") (pin "2") (pinfunction "2_2") (pintype "passive"))
      (node (ref "FR14") (pin "2") (pinfunction "2_2") (pintype "passive"))
      (node (ref "IC1") (pin "K6") (pinfunction "VDD12_VCO_SXT_K6") (pintype "passive"))
      (node (ref "R28") (pin "2") (pinfunction "2_2") (pintype "passive"))
    )
    (net (code "26") (name "Net-(IC1B-VDD14_LNA_RFE)") (class "Default")
      (node (ref "C78") (pin "1") (pinfunction "1_1") (pintype "passive"))
      (node (ref "FR33") (pin "1") (pinfunction "1_1") (pintype "passive"))
      (node (ref "IC1") (pin "AF6") (pinfunction "VDD14_LNA_RFE_AF6") (pintype "passive"))
    )
    (net (code "27") (name "Net-(IC1B-VDD14_RBB)") (class "Default")
      (node (ref "C79") (pin "1") (pinfunction "1_1") (pintype "passive"))
      (node (ref "FR34") (pin "1") (pinfunction "1_1") (pintype "passive"))
      (node (ref "IC1") (pin "AD4") (pinfunction "VDD14_RBB_AD4") (pintype "passive"))
    )
    (net (code "28") (name "Net-(IC1B-VDD14_TIA_RFE)") (class "Default")
      (node (ref "C80") (pin "1") (pinfunction "1_1") (pintype "passive"))
      (node (ref "FR35") (pin "1") (pinfunction "1_1") (pintype "passive"))
      (node (ref "IC1") (pin "AF2") (pinfunction "VDD14_TIA_RFE_AF2") (pintype "passive"))
    )
    (net (code "29") (name "Net-(IC1B-VDD14_VCO_CGEN)") (class "Default")
      (node (ref "C56") (pin "1") (pinfunction "1_1") (pintype "passive"))
      (node (ref "FR17") (pin "1") (pinfunction "1_1") (pintype "passive"))
      (node (ref "IC1") (pin "C21") (pinfunction "VDD14_VCO_CGEN_C21") (pintype "passive"))
    )
    (net (code "30") (name "Net-(IC1B-VDD18_BIAS)") (class "Default")
      (node (ref "C46") (pin "1") (pinfunction "1_1") (pintype "passive"))
      (node (ref "FR3") (pin "1") (pinfunction "1_1") (pintype "passive"))
      (node (ref "IC1") (pin "E17") (pinfunction "VDD18_BIAS_E17") (pintype "passive"))
    )
    (net (code "31") (name "Net-(IC1B-VDD18_DIG)") (class "Default")
      (node (ref "C41") (pin "1") (pinfunction "1_1") (pintype "passive"))
      (node (ref "IC1") (pin "D24") (pinfunction "VDD18_DIG_D24") (pintype "passive"))
      (node (ref "R25") (pin "1") (pinfunction "1_1") (pintype "passive"))
    )
    (net (code "32") (name "Net-(IC1B-VDD18_LDO_RX)") (class "Default")
      (node (ref "C68") (pin "1") (pinfunction "1_1") (pintype "passive"))
      (node (ref "FR23") (pin "2") (pinfunction "2_2") (pintype "passive"))
      (node (ref "IC1") (pin "AE3") (pinfunction "VDD18_TIA_RFE_AE3") (pintype "passive"))
      (node (ref "IC1") (pin "AF4") (pinfunction "VDD18_LDO_RX_AF4") (pintype "passive"))
    )
    (net (code "33") (name "Net-(IC1B-VDD18_LDO_TX)") (class "Default")
      (node (ref "C62") (pin "1") (pinfunction "1_1") (pintype "passive"))
      (node (ref "FR21") (pin "2") (pinfunction "2_2") (pintype "passive"))
      (node (ref "IC1") (pin "N1") (pinfunction "VDD18_LDO_TX_N1") (pintype "passive"))
    )
    (net (code "34") (name "Net-(IC1B-VDD18_RXBUF)") (class "Default")
      (node (ref "C75") (pin "1") (pinfunction "1_1") (pintype "passive"))
      (node (ref "FR31") (pin "1") (pinfunction "1_1") (pintype "passive"))
      (node (ref "IC1") (pin "AM26") (pinfunction "VDD18_RXBUF_AM26") (pintype "passive"))
    )
    (net (code "35") (name "Net-(IC1B-VDD18_SXR)") (class "Default")
      (node (ref "C63") (pin "1") (pinfunction "1_1") (pintype "passive"))
      (node (ref "FR19") (pin "1") (pinfunction "1_1") (pintype "passive"))
      (node (ref "IC1") (pin "AM18") (pinfunction "VDD18_SXR_AM18") (pintype "passive"))
    )
    (net (code "36") (name "Net-(IC1B-VDD18_TRF)") (class "Default")
      (node (ref "C45") (pin "1") (pinfunction "1_1") (pintype "passive"))
      (node (ref "FR6") (pin "1") (pinfunction "1_1") (pintype "passive"))
      (node (ref "IC1") (pin "D16") (pinfunction "VDD18_TRF_D16") (pintype "passive"))
    )
    (net (code "37") (name "Net-(IC1B-VDD18_TXBUF)") (class "Default")
      (node (ref "C50") (pin "1") (pinfunction "1_1") (pintype "passive"))
      (node (ref "FR10") (pin "2") (pinfunction "2_2") (pintype "passive"))
      (node (ref "IC1") (pin "H6") (pinfunction "VDD18_TXBUF_H6") (pintype "passive"))
    )
    (net (code "38") (name "Net-(IC1B-VDD18_VCO_CGEN)") (class "Default")
      (node (ref "C44") (pin "1") (pinfunction "1_1") (pintype "passive"))
      (node (ref "FR7") (pin "1") (pinfunction "1_1") (pintype "passive"))
      (node (ref "IC1") (pin "E21") (pinfunction "VDD18_VCO_CGEN_E21") (pintype "passive"))
    )
    (net (code "39") (name "Net-(IC1B-VDD18_VCO_SXR)") (class "Default")
      (node (ref "C77") (pin "1") (pinfunction "1_1") (pintype "passive"))
      (node (ref "FR32") (pin "1") (pinfunction "1_1") (pintype "passive"))
      (node (ref "IC1") (pin "AK22") (pinfunction "VDD18_VCO_SXR_AK22") (pintype "passive"))
    )
    (net (code "40") (name "Net-(IC1B-VDD18_VCO_SXT)") (class "Default")
      (node (ref "C48") (pin "1") (pinfunction "1_1") (pintype "passive"))
      (node (ref "FR12") (pin "1") (pinfunction "1_1") (pintype "passive"))
      (node (ref "IC1") (pin "G3") (pinfunction "VDD18_VCO_SXT_G3") (pintype "passive"))
    )
    (net (code "41") (name "Net-(IC1B-VDDO_DIV_SXT)") (class "Default")
      (node (ref "IC1") (pin "K2") (pinfunction "VDDO_DIV_SXT_K2") (pintype "passive"))
      (node (ref "R31") (pin "1") (pinfunction "1_1") (pintype "passive"))
    )
    (net (code "42") (name "Net-(IC1B-VDDO_TLOBUF_TRF)") (class "Default")
      (node (ref "IC1") (pin "D6") (pinfunction "VDDO_TLOBUF_TRF_D6") (pintype "passive"))
      (node (ref "R26") (pin "2") (pinfunction "2_2") (pintype "passive"))
    )
    (net (code "43") (name "Net-(IC1B-VDD_AFE)") (class "Default")
      (node (ref "C70") (pin "1") (pinfunction "1_1") (pintype "passive"))
      (node (ref "FR26") (pin "1") (pinfunction "1_1") (pintype "passive"))
      (node (ref "IC1") (pin "AJ25") (pinfunction "VDD_AFE_AJ25") (pintype "passive"))
    )
    (net (code "44") (name "Net-(IC1B-VDD_CP_CGEN)") (class "Default")
      (node (ref "C57") (pin "1") (pinfunction "1_1") (pintype "passive"))
      (node (ref "IC1") (pin "F20") (pinfunction "VDD_CP_CGEN_F20") (pintype "passive"))
      (node (ref "R29") (pin "2") (pinfunction "2_2") (pintype "passive"))
    )
    (net (code "45") (name "Net-(IC1B-VDD_CP_SXR)") (class "Default")
      (node (ref "C64") (pin "1") (pinfunction "1_1") (pintype "passive"))
      (node (ref "IC1") (pin "AL19") (pinfunction "VDD_CP_SXR_AL19") (pintype "passive"))
      (node (ref "R32") (pin "2") (pinfunction "2_2") (pintype "passive"))
    )
    (net (code "46") (name "Net-(IC1B-VDD_CP_SXT)") (class "Default")
      (node (ref "C55") (pin "1") (pinfunction "1_1") (pintype "passive"))
      (node (ref "IC1") (pin "J3") (pinfunction "VDD_CP_SXT_J3") (pintype "passive"))
      (node (ref "R30") (pin "1") (pinfunction "1_1") (pintype "passive"))
    )
    (net (code "47") (name "Net-(IC1B-VDD_DIV_CGEN)") (class "Default")
      (node (ref "C54") (pin "1") (pinfunction "1_1") (pintype "passive"))
      (node (ref "FR13") (pin "1") (pinfunction "1_1") (pintype "passive"))
      (node (ref "IC1") (pin "E19") (pinfunction "VDD_DIV_CGEN_E19") (pintype "passive"))
    )
    (net (code "48") (name "Net-(IC1B-VDD_DIV_SXR)") (class "Default")
      (node (ref "C66") (pin "1") (pinfunction "1_1") (pintype "passive"))
      (node (ref "FR22") (pin "1") (pinfunction "1_1") (pintype "passive"))
      (node (ref "IC1") (pin "AM20") (pinfunction "VDD_DIV_SXR_AM20") (pintype "passive"))
    )
    (net (code "49") (name "Net-(IC1B-VDD_DIV_SXT)") (class "Default")
      (node (ref "C59") (pin "1") (pinfunction "1_1") (pintype "passive"))
      (node (ref "FR16") (pin "2") (pinfunction "2_2") (pintype "passive"))
      (node (ref "FR18") (pin "2") (pinfunction "2_2") (pintype "passive"))
      (node (ref "IC1") (pin "L5") (pinfunction "VDD_DIV_SXT_L5") (pintype "passive"))
      (node (ref "R31") (pin "2") (pinfunction "2_2") (pintype "passive"))
    )
    (net (code "50") (name "Net-(IC1B-VDD_MXLOBUF_RFE)") (class "Default")
      (node (ref "C69") (pin "1") (pinfunction "1_1") (pintype "passive"))
      (node (ref "FR24") (pin "1") (pinfunction "1_1") (pintype "passive"))
      (node (ref "FR25") (pin "1") (pinfunction "1_1") (pintype "passive"))
      (node (ref "IC1") (pin "AN17") (pinfunction "VDD_MXLOBUF_RFE_AN17") (pintype "passive"))
    )
    (net (code "51") (name "Net-(IC1B-VDD_SPI_BUF)") (class "Default")
      (node (ref "C43") (pin "1") (pinfunction "1_1") (pintype "passive"))
      (node (ref "FR4") (pin "2") (pinfunction "2_2") (pintype "passive"))
      (node (ref "IC1") (pin "F24") (pinfunction "VDD_SPI_BUF_F24") (pintype "passive"))
    )
    (net (code "52") (name "Net-(IC1B-VDD_TBB)") (class "Default")
      (node (ref "C72") (pin "1") (pinfunction "1_1") (pintype "passive"))
      (node (ref "FR30") (pin "2") (pinfunction "2_2") (pintype "passive"))
      (node (ref "IC1") (pin "P4") (pinfunction "VDD_TBB_P4") (pintype "passive"))
    )
    (net (code "53") (name "Net-(IC1B-VDD_TLOBUF_TRF)") (class "Default")
      (node (ref "C42") (pin "1") (pinfunction "1_1") (pintype "passive"))
      (node (ref "FR1") (pin "1") (pinfunction "1_1") (pintype "passive"))
      (node (ref "IC1") (pin "F8") (pinfunction "VDD_TLOBUF_TRF_F8") (pintype "passive"))
      (node (ref "R26") (pin "1") (pinfunction "1_1") (pintype "passive"))
    )
    (net (code "54") (name "Net-(IC1B-VDD_TPAD_TRF)") (class "Default")
      (node (ref "C51") (pin "1") (pinfunction "1_1") (pintype "passive"))
      (node (ref "FR8") (pin "1") (pinfunction "1_1") (pintype "passive"))
      (node (ref "IC1") (pin "B16") (pinfunction "VDD_TPAD_TRF_B16") (pintype "passive"))
    )
    (net (code "55") (name "VCC1P4_LMS") (class "Default")
      (node (ref "FR16") (pin "1") (pinfunction "1_1") (pintype "passive"))
      (node (ref "FR17") (pin "2") (pinfunction "2_2") (pintype "passive"))
      (node (ref "FR24") (pin "2") (pinfunction "2_2") (pintype "passive"))
      (node (ref "FR33") (pin "2") (pinfunction "2_2") (pintype "passive"))
      (node (ref "FR34") (pin "2") (pinfunction "2_2") (pintype "passive"))
      (node (ref "FR35") (pin "2") (pinfunction "2_2") (pintype "passive"))
    )
    (net (code "56") (name "VCC1P8_LMS") (class "Default")
      (node (ref "FR12") (pin "2") (pinfunction "2_2") (pintype "passive"))
      (node (ref "FR19") (pin "2") (pinfunction "2_2") (pintype "passive"))
      (node (ref "FR21") (pin "1") (pinfunction "1_1") (pintype "passive"))
      (node (ref "FR23") (pin "1") (pinfunction "1_1") (pintype "passive"))
      (node (ref "FR3") (pin "2") (pinfunction "2_2") (pintype "passive"))
      (node (ref "FR32") (pin "2") (pinfunction "2_2") (pintype "passive"))
      (node (ref "FR6") (pin "2") (pinfunction "2_2") (pintype "passive"))
      (node (ref "FR7") (pin "2") (pinfunction "2_2") (pintype "passive"))
      (node (ref "R25") (pin "2") (pinfunction "2_2") (pintype "passive"))
      (node (ref "R27") (pin "2") (pinfunction "2_2") (pintype "passive"))
      (node (ref "R35") (pin "1") (pinfunction "1_1") (pintype "passive"))
    )
    (net (code "57") (name "VCC1P25_LMS") (class "Default")
      (node (ref "FR1") (pin "2") (pinfunction "2_2") (pintype "passive"))
      (node (ref "FR11") (pin "2") (pinfunction "2_2") (pintype "passive"))
      (node (ref "FR13") (pin "2") (pinfunction "2_2") (pintype "passive"))
      (node (ref "FR14") (pin "1") (pinfunction "1_1") (pintype "passive"))
      (node (ref "FR15") (pin "2") (pinfunction "2_2") (pintype "passive"))
      (node (ref "FR18") (pin "1") (pinfunction "1_1") (pintype "passive"))
      (node (ref "FR2") (pin "1") (pinfunction "1_1") (pintype "passive"))
      (node (ref "FR22") (pin "2") (pinfunction "2_2") (pintype "passive"))
      (node (ref "FR25") (pin "2") (pinfunction "2_2") (pintype "passive"))
      (node (ref "FR26") (pin "2") (pinfunction "2_2") (pintype "passive"))
      (node (ref "FR27") (pin "1") (pinfunction "1_1") (pintype "passive"))
      (node (ref "FR28") (pin "1") (pinfunction "1_1") (pintype "passive"))
      (node (ref "FR30") (pin "1") (pinfunction "1_1") (pintype "passive"))
      (node (ref "FR4") (pin "1") (pinfunction "1_1") (pintype "passive"))
      (node (ref "FR5") (pin "1") (pinfunction "1_1") (pintype "passive"))
      (node (ref "FR8") (pin "2") (pinfunction "2_2") (pintype "passive"))
      (node (ref "FR9") (pin "1") (pinfunction "1_1") (pintype "passive"))
      (node (ref "R29") (pin "1") (pinfunction "1_1") (pintype "passive"))
      (node (ref "R30") (pin "2") (pinfunction "2_2") (pintype "passive"))
      (node (ref "R32") (pin "1") (pinfunction "1_1") (pintype "passive"))
      (node (ref "R33") (pin "2") (pinfunction "2_2") (pintype "passive"))
      (node (ref "R34") (pin "1") (pinfunction "1_1") (pintype "passive"))
    )
    (net (code "58") (name "VCC1P25_LMS_DIG") (class "Default")
      (node (ref "R16") (pin "2") (pinfunction "2_2") (pintype "passive"))
      (node (ref "R18") (pin "2") (pinfunction "2_2") (pintype "passive"))
      (node (ref "R20") (pin "2") (pinfunction "2_2") (pintype "passive"))
      (node (ref "R22") (pin "2") (pinfunction "2_2") (pintype "passive"))
    )
    (net (code "59") (name "VDIO_LMS") (class "Default")
      (node (ref "R17") (pin "1") (pinfunction "1_1") (pintype "passive"))
      (node (ref "R19") (pin "1") (pinfunction "1_1") (pintype "passive"))
      (node (ref "R21") (pin "1") (pinfunction "1_1") (pintype "passive"))
      (node (ref "R23") (pin "1") (pinfunction "1_1") (pintype "passive"))
      (node (ref "R24") (pin "1") (pinfunction "1_1") (pintype "passive"))
    )
  )
)
